# Sensor_LM35_Connector.net
KiCad netlist of a schematic drawn in Altium Designer
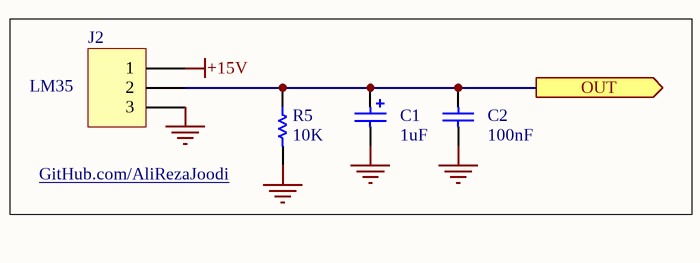
[diagram p0: Sensor_LM35_Connector.SchDoc]

(export (version "E")
  (design (tool "Eeschema 10.0.6"))
  (components
    (comp (ref "C1")
      (value "1uF")
      (footprint "CAPPR2.5-6.3x5")
      (description "Polarized Capacitor (Radial)")
      (fields (field (name "MANUFACTURER") "Generic Components") (field (name "PUBLISHER") "Altium Limited"))
      (libsource (lib "Miscellaneous Devices") (part "Cap Pol1"))
    )
    (comp (ref "C2")
      (value "100nF")
      (footprint "CAPNTO2.54-3.05x1.78A")
      (description "Capacitor")
      (fields (field (name "MANUFACTURER") "Generic Components") (field (name "PUBLISHER") "Altium Limited"))
      (libsource (lib "Miscellaneous Devices") (part "Cap"))
    )
    (comp (ref "J2")
      (value "3PIN")
      (footprint "Fonics_3PIN_1")
      (description "Header, 3-Pin")
      (fields (field (name "MANUFACTURER") "Generic Components") (field (name "PUBLISHER") "Altium Limited"))
      (libsource (lib "Miscellaneous Connectors") (part "Header 3"))
    )
    (comp (ref "R5")
      (value "10K")
      (footprint "AXIAL-0.4")
      (description "Resistor")
      (fields (field (name "PUBLISHER") "Altium Limited"))
      (libsource (lib "Miscellaneous Devices") (part "Res1"))
    )
  )
  (nets
    (net (code "1") (name "+15V") (class "Default")
      (node (ref "J2") (pin "1") (pinfunction "1_1") (pintype "passive"))
    )
    (net (code "2") (name "/OUT") (class "Default")
      (node (ref "C1") (pin "1") (pinfunction "1_1") (pintype "passive"))
      (node (ref "C2") (pin "2") (pinfunction "2_2") (pintype "passive"))
      (node (ref "J2") (pin "2") (pinfunction "2_2") (pintype "passive"))
      (node (ref "R5") (pin "1") (pinfunction "1_1") (pintype "passive"))
    )
    (net (code "3") (name "GND") (class "Default")
      (node (ref "C1") (pin "2") (pinfunction "2_2") (pintype "passive"))
      (node (ref "C2") (pin "1") (pinfunction "1_1") (pintype "passive"))
      (node (ref "J2") (pin "3") (pinfunction "3_3") (pintype "passive"))
      (node (ref "R5") (pin "2") (pinfunction "2_2") (pintype "passive"))
    )
  )
)
